# P2H3-001.net
KiCad netlist of a schematic drawn in EAGLE
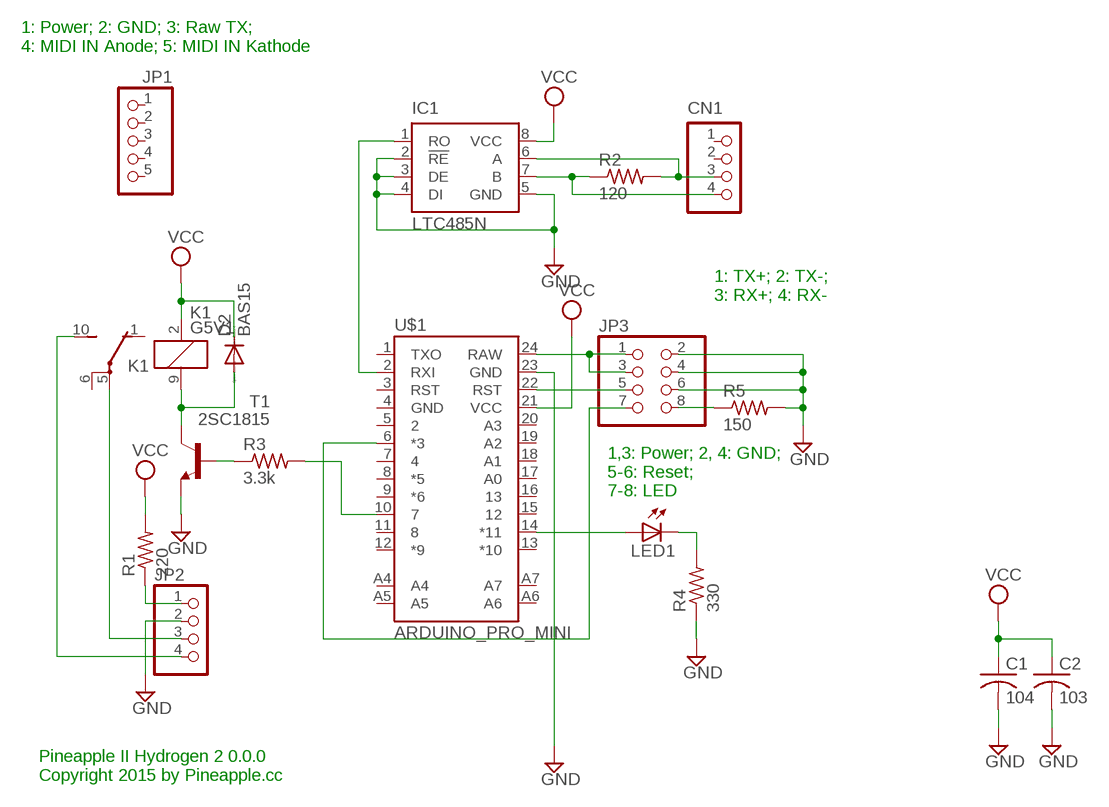
[diagram p0: schematic, sheet 1]

(export (version "E")
  (design (tool "Eeschema 10.0.6"))
  (components
    (comp (ref "C1")
      (value "104")
      (footprint "eagle-import:C025-025X050")
      (libsource (lib "eagle-import") (part "C-US025-025X050"))
    )
    (comp (ref "C2")
      (value "103")
      (footprint "eagle-import:C025-025X050")
      (libsource (lib "eagle-import") (part "C-US025-025X050"))
    )
    (comp (ref "CN1")
      (value "B4B-PH-K-S")
      (footprint "eagle-import:B4B-PH-K-S")
      (libsource (lib "eagle-import") (part "B4B-PH-K-S"))
    )
    (comp (ref "D2")
      (value "BAS15")
      (footprint "eagle-import:DO34-7")
      (libsource (lib "eagle-import") (part "BAS15"))
    )
    (comp (ref "IC1")
      (value "LTC485N")
      (footprint "eagle-import:DIL08")
      (libsource (lib "eagle-import") (part "LTC485N"))
    )
    (comp (ref "JP1")
      (value "PINHD-1X5")
      (footprint "eagle-import:1X05")
      (libsource (lib "eagle-import") (part "PINHD-1X5"))
    )
    (comp (ref "JP2")
      (value "PINHD-1X4")
      (footprint "eagle-import:1X04")
      (libsource (lib "eagle-import") (part "PINHD-1X4"))
    )
    (comp (ref "JP3")
      (value "PINHD-2X4")
      (footprint "eagle-import:2X04")
      (libsource (lib "eagle-import") (part "PINHD-2X4"))
    )
    (comp (ref "K1")
      (value "G5V1")
      (footprint "eagle-import:G5V1")
      (fields (field (name "MPN") "G5V-1-DC24"))
      (libsource (lib "eagle-import") (part "G5V1"))
    )
    (comp (ref "LED1")
      (value "LED3MM")
      (footprint "eagle-import:LED3MM")
      (libsource (lib "eagle-import") (part "LED3MM"))
    )
    (comp (ref "R1")
      (value "220")
      (footprint "eagle-import:0204_5")
      (libsource (lib "eagle-import") (part "R-US_0204/5"))
    )
    (comp (ref "R2")
      (value "120")
      (footprint "eagle-import:0204_5")
      (libsource (lib "eagle-import") (part "R-US_0204/5"))
    )
    (comp (ref "R3")
      (value "3.3k")
      (footprint "eagle-import:0204_5")
      (libsource (lib "eagle-import") (part "R-US_0204/5"))
    )
    (comp (ref "R4")
      (value "330")
      (footprint "eagle-import:0204_5")
      (libsource (lib "eagle-import") (part "R-US_0204/5"))
    )
    (comp (ref "R5")
      (value "150")
      (footprint "eagle-import:0204_5")
      (libsource (lib "eagle-import") (part "R-US_0204/5"))
    )
    (comp (ref "T1")
      (value "2SC1815")
      (footprint "eagle-import:TO92-ECB")
      (libsource (lib "eagle-import") (part "2SC1815"))
    )
    (comp (ref "U$1")
      (value "ARDUINO_PRO_MINI")
      (footprint "eagle-import:ARDUINO_PRO_MINI")
      (libsource (lib "eagle-import") (part "ARDUINO_PRO_MINI"))
    )
  )
  (nets
    (net (code "1") (name "GND") (class "Default")
      (node (ref "C1") (pin "2") (pinfunction "2_2") (pintype "passive"))
      (node (ref "C2") (pin "2") (pinfunction "2_2") (pintype "passive"))
      (node (ref "IC1") (pin "2") (pinfunction "~{RE}_2") (pintype "input"))
      (node (ref "IC1") (pin "3") (pinfunction "DE_3") (pintype "input"))
      (node (ref "IC1") (pin "4") (pinfunction "DI_4") (pintype "input"))
      (node (ref "IC1") (pin "5") (pinfunction "GND_5") (pintype "input"))
      (node (ref "JP2") (pin "2") (pinfunction "2_2") (pintype "passive"))
      (node (ref "JP3") (pin "2") (pinfunction "2_2") (pintype "passive"))
      (node (ref "JP3") (pin "4") (pinfunction "4_4") (pintype "passive"))
      (node (ref "JP3") (pin "6") (pinfunction "6_6") (pintype "passive"))
      (node (ref "R4") (pin "1") (pinfunction "1_1") (pintype "passive"))
      (node (ref "R5") (pin "2") (pinfunction "2_2") (pintype "passive"))
      (node (ref "T1") (pin "E") (pinfunction "E_E") (pintype "passive"))
      (node (ref "U$1") (pin "23") (pinfunction "GND_23") (pintype "bidirectional"))
    )
    (net (code "2") (name "Net-(IC1-A)") (class "Default")
      (node (ref "CN1") (pin "3") (pinfunction "3_3") (pintype "passive"))
      (node (ref "IC1") (pin "6") (pinfunction "A_6") (pintype "bidirectional"))
      (node (ref "R2") (pin "2") (pinfunction "2_2") (pintype "passive"))
    )
    (net (code "3") (name "Net-(IC1-B)") (class "Default")
      (node (ref "CN1") (pin "4") (pinfunction "4_4") (pintype "passive"))
      (node (ref "IC1") (pin "7") (pinfunction "B_7") (pintype "bidirectional"))
      (node (ref "R2") (pin "1") (pinfunction "1_1") (pintype "passive"))
    )
    (net (code "4") (name "Net-(IC1-RO)") (class "Default")
      (node (ref "IC1") (pin "1") (pinfunction "RO_1") (pintype "output"))
      (node (ref "U$1") (pin "2") (pinfunction "RXI_2") (pintype "bidirectional"))
    )
    (net (code "5") (name "Net-(JP2-Pad1)") (class "Default")
      (node (ref "JP2") (pin "1") (pinfunction "1_1") (pintype "passive"))
      (node (ref "R1") (pin "1") (pinfunction "1_1") (pintype "passive"))
    )
    (net (code "6") (name "Net-(JP2-Pad3)") (class "Default")
      (node (ref "JP2") (pin "3") (pinfunction "3_3") (pintype "passive"))
      (node (ref "K1") (pin "5") (pinfunction "P_5") (pintype "passive"))
    )
    (net (code "7") (name "Net-(JP3-Pad5)") (class "Default")
      (node (ref "JP3") (pin "5") (pinfunction "5_5") (pintype "passive"))
      (node (ref "U$1") (pin "22") (pinfunction "RST_22") (pintype "bidirectional"))
    )
    (net (code "8") (name "Net-(JP3-Pad8)") (class "Default")
      (node (ref "JP3") (pin "8") (pinfunction "8_8") (pintype "passive"))
      (node (ref "R5") (pin "1") (pinfunction "1_1") (pintype "passive"))
    )
    (net (code "9") (name "Net-(K1A-2)") (class "Default")
      (node (ref "D2") (pin "A") (pinfunction "A_A") (pintype "passive"))
      (node (ref "K1") (pin "9") (pinfunction "2_9") (pintype "passive"))
      (node (ref "T1") (pin "C") (pinfunction "C_C") (pintype "passive"))
    )
    (net (code "10") (name "Net-(K1B-S)") (class "Default")
      (node (ref "JP2") (pin "4") (pinfunction "4_4") (pintype "passive"))
      (node (ref "K1") (pin "10") (pinfunction "S_10") (pintype "passive"))
    )
    (net (code "11") (name "Net-(LED1-C)") (class "Default")
      (node (ref "LED1") (pin "K") (pinfunction "C_K") (pintype "passive"))
      (node (ref "R4") (pin "2") (pinfunction "2_2") (pintype "passive"))
    )
    (net (code "12") (name "Net-(R3-Pad1)") (class "Default")
      (node (ref "R3") (pin "1") (pinfunction "1_1") (pintype "passive"))
      (node (ref "T1") (pin "B") (pinfunction "B_B") (pintype "passive"))
    )
    (net (code "13") (name "Net-(U$1-*3)") (class "Default")
      (node (ref "JP3") (pin "7") (pinfunction "7_7") (pintype "passive"))
      (node (ref "U$1") (pin "6") (pinfunction "*3_6") (pintype "bidirectional"))
    )
    (net (code "14") (name "Net-(U$1-*11)") (class "Default")
      (node (ref "LED1") (pin "A") (pinfunction "A_A") (pintype "passive"))
      (node (ref "U$1") (pin "14") (pinfunction "*11_14") (pintype "bidirectional"))
    )
    (net (code "15") (name "Net-(U$1-7)") (class "Default")
      (node (ref "R3") (pin "2") (pinfunction "2_2") (pintype "passive"))
      (node (ref "U$1") (pin "10") (pinfunction "7_10") (pintype "bidirectional"))
    )
    (net (code "16") (name "Net-(U$1-RAW)") (class "Default")
      (node (ref "JP3") (pin "1") (pinfunction "1_1") (pintype "passive"))
      (node (ref "JP3") (pin "3") (pinfunction "3_3") (pintype "passive"))
      (node (ref "U$1") (pin "24") (pinfunction "RAW_24") (pintype "bidirectional"))
    )
    (net (code "17") (name "VCC") (class "Default")
      (node (ref "C1") (pin "1") (pinfunction "1_1") (pintype "passive"))
      (node (ref "C2") (pin "1") (pinfunction "1_1") (pintype "passive"))
      (node (ref "D2") (pin "C") (pinfunction "C_C") (pintype "passive"))
      (node (ref "IC1") (pin "8") (pinfunction "VCC_8") (pintype "input"))
      (node (ref "K1") (pin "2") (pinfunction "1_2") (pintype "passive"))
      (node (ref "R1") (pin "2") (pinfunction "2_2") (pintype "passive"))
      (node (ref "U$1") (pin "21") (pinfunction "VCC_21") (pintype "bidirectional"))
    )
    (net (code "18") (name "unconnected-(CN1-Pad1)") (class "Default")
      (node (ref "CN1") (pin "1") (pinfunction "1_1") (pintype "passive"))
    )
    (net (code "19") (name "unconnected-(CN1-Pad2)") (class "Default")
      (node (ref "CN1") (pin "2") (pinfunction "2_2") (pintype "passive"))
    )
    (net (code "20") (name "unconnected-(JP1-Pad1)") (class "Default")
      (node (ref "JP1") (pin "1") (pinfunction "1_1") (pintype "passive"))
    )
    (net (code "21") (name "unconnected-(JP1-Pad2)") (class "Default")
      (node (ref "JP1") (pin "2") (pinfunction "2_2") (pintype "passive"))
    )
    (net (code "22") (name "unconnected-(JP1-Pad3)") (class "Default")
      (node (ref "JP1") (pin "3") (pinfunction "3_3") (pintype "passive"))
    )
    (net (code "23") (name "unconnected-(JP1-Pad4)") (class "Default")
      (node (ref "JP1") (pin "4") (pinfunction "4_4") (pintype "passive"))
    )
    (net (code "24") (name "unconnected-(JP1-Pad5)") (class "Default")
      (node (ref "JP1") (pin "5") (pinfunction "5_5") (pintype "passive"))
    )
    (net (code "25") (name "unconnected-(K1B-O-Pad1)") (class "Default")
      (node (ref "K1") (pin "1") (pinfunction "O_1") (pintype "passive"))
    )
    (net (code "26") (name "unconnected-(K1B-P-Pad6)") (class "Default")
      (node (ref "K1") (pin "6") (pinfunction "P_6") (pintype "passive"))
    )
    (net (code "27") (name "unconnected-(U$1-*5-Pad8)") (class "Default")
      (node (ref "U$1") (pin "8") (pinfunction "*5_8") (pintype "bidirectional"))
    )
    (net (code "28") (name "unconnected-(U$1-*6-Pad9)") (class "Default")
      (node (ref "U$1") (pin "9") (pinfunction "*6_9") (pintype "bidirectional"))
    )
    (net (code "29") (name "unconnected-(U$1-*9-Pad12)") (class "Default")
      (node (ref "U$1") (pin "12") (pinfunction "*9_12") (pintype "bidirectional"))
    )
    (net (code "30") (name "unconnected-(U$1-*10-Pad13)") (class "Default")
      (node (ref "U$1") (pin "13") (pinfunction "*10_13") (pintype "bidirectional"))
    )
    (net (code "31") (name "unconnected-(U$1-2-Pad5)") (class "Default")
      (node (ref "U$1") (pin "5") (pinfunction "2_5") (pintype "bidirectional"))
    )
    (net (code "32") (name "unconnected-(U$1-4-Pad7)") (class "Default")
      (node (ref "U$1") (pin "7") (pinfunction "4_7") (pintype "bidirectional"))
    )
    (net (code "33") (name "unconnected-(U$1-8-Pad11)") (class "Default")
      (node (ref "U$1") (pin "11") (pinfunction "8_11") (pintype "bidirectional"))
    )
    (net (code "34") (name "unconnected-(U$1-12-Pad15)") (class "Default")
      (node (ref "U$1") (pin "15") (pinfunction "12_15") (pintype "bidirectional"))
    )
    (net (code "35") (name "unconnected-(U$1-13-Pad16)") (class "Default")
      (node (ref "U$1") (pin "16") (pinfunction "13_16") (pintype "bidirectional"))
    )
    (net (code "36") (name "unconnected-(U$1-A0-Pad17)") (class "Default")
      (node (ref "U$1") (pin "17") (pinfunction "A0_17") (pintype "bidirectional"))
    )
    (net (code "37") (name "unconnected-(U$1-A1-Pad18)") (class "Default")
      (node (ref "U$1") (pin "18") (pinfunction "A1_18") (pintype "bidirectional"))
    )
    (net (code "38") (name "unconnected-(U$1-A2-Pad19)") (class "Default")
      (node (ref "U$1") (pin "19") (pinfunction "A2_19") (pintype "bidirectional"))
    )
    (net (code "39") (name "unconnected-(U$1-A3-Pad20)") (class "Default")
      (node (ref "U$1") (pin "20") (pinfunction "A3_20") (pintype "bidirectional"))
    )
    (net (code "40") (name "unconnected-(U$1-GND-Pad4)") (class "Default")
      (node (ref "U$1") (pin "4") (pinfunction "GND_4") (pintype "bidirectional"))
    )
    (net (code "41") (name "unconnected-(U$1-PadA4)") (class "Default")
      (node (ref "U$1") (pin "A4") (pinfunction "A4_A4") (pintype "bidirectional"))
    )
    (net (code "42") (name "unconnected-(U$1-PadA5)") (class "Default")
      (node (ref "U$1") (pin "A5") (pinfunction "A5_A5") (pintype "bidirectional"))
    )
    (net (code "43") (name "unconnected-(U$1-PadA6)") (class "Default")
      (node (ref "U$1") (pin "A6") (pinfunction "A6_A6") (pintype "bidirectional"))
    )
    (net (code "44") (name "unconnected-(U$1-PadA7)") (class "Default")
      (node (ref "U$1") (pin "A7") (pinfunction "A7_A7") (pintype "bidirectional"))
    )
    (net (code "45") (name "unconnected-(U$1-RST-Pad3)") (class "Default")
      (node (ref "U$1") (pin "3") (pinfunction "RST_3") (pintype "bidirectional"))
    )
    (net (code "46") (name "unconnected-(U$1-TXO-Pad1)") (class "Default")
      (node (ref "U$1") (pin "1") (pinfunction "TXO_1") (pintype "bidirectional"))
    )
  )
)
